# voltage_monitor.net
KiCad netlist of a schematic drawn in EAGLE
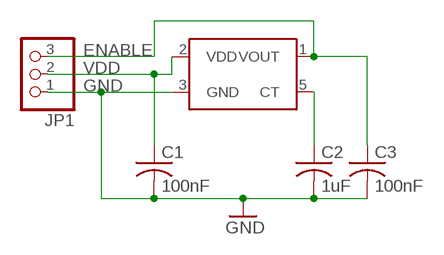
[diagram p0: schematic, sheet 1]

(export (version "E")
  (design (tool "Eeschema 10.0.6"))
  (components
    (comp (ref "C1")
      (value "100nF")
      (footprint "eagle-import:C1206")
      (libsource (lib "eagle-import") (part "C-USC1206"))
    )
    (comp (ref "C2")
      (value "1uF")
      (footprint "eagle-import:C1206")
      (libsource (lib "eagle-import") (part "C-USC1206"))
    )
    (comp (ref "C3")
      (value "100nF")
      (footprint "eagle-import:C1206")
      (libsource (lib "eagle-import") (part "C-USC1206"))
    )
    (comp (ref "JP1")
      (value "PINHD-1X3")
      (footprint "eagle-import:1X03")
      (libsource (lib "eagle-import") (part "PINHD-1X3"))
    )
    (comp (ref "U$1")
      (value "BD5260G")
      (footprint "eagle-import:SOT23-5")
      (libsource (lib "eagle-import") (part "BD5260G"))
    )
  )
  (nets
    (net (code "1") (name "/ENABLE") (class "Default")
      (node (ref "C3") (pin "1") (pinfunction "1_1") (pintype "passive"))
      (node (ref "JP1") (pin "3") (pinfunction "3_3") (pintype "passive"))
      (node (ref "U$1") (pin "1") (pinfunction "VOUT_1") (pintype "bidirectional"))
    )
    (net (code "2") (name "/VDD") (class "Default")
      (node (ref "C1") (pin "1") (pinfunction "1_1") (pintype "passive"))
      (node (ref "JP1") (pin "2") (pinfunction "2_2") (pintype "passive"))
      (node (ref "U$1") (pin "2") (pinfunction "VDD_2") (pintype "bidirectional"))
    )
    (net (code "3") (name "GND") (class "Default")
      (node (ref "C1") (pin "2") (pinfunction "2_2") (pintype "passive"))
      (node (ref "C2") (pin "2") (pinfunction "2_2") (pintype "passive"))
      (node (ref "C3") (pin "2") (pinfunction "2_2") (pintype "passive"))
      (node (ref "JP1") (pin "1") (pinfunction "1_1") (pintype "passive"))
      (node (ref "U$1") (pin "3") (pinfunction "GND_3") (pintype "bidirectional"))
    )
    (net (code "4") (name "Net-(U$1-CT)") (class "Default")
      (node (ref "C2") (pin "1") (pinfunction "1_1") (pintype "passive"))
      (node (ref "U$1") (pin "5") (pinfunction "CT_5") (pintype "bidirectional"))
    )
  )
)
